# Arduino_Basic_Sensor_Board.net
KiCad netlist of a schematic drawn in EAGLE
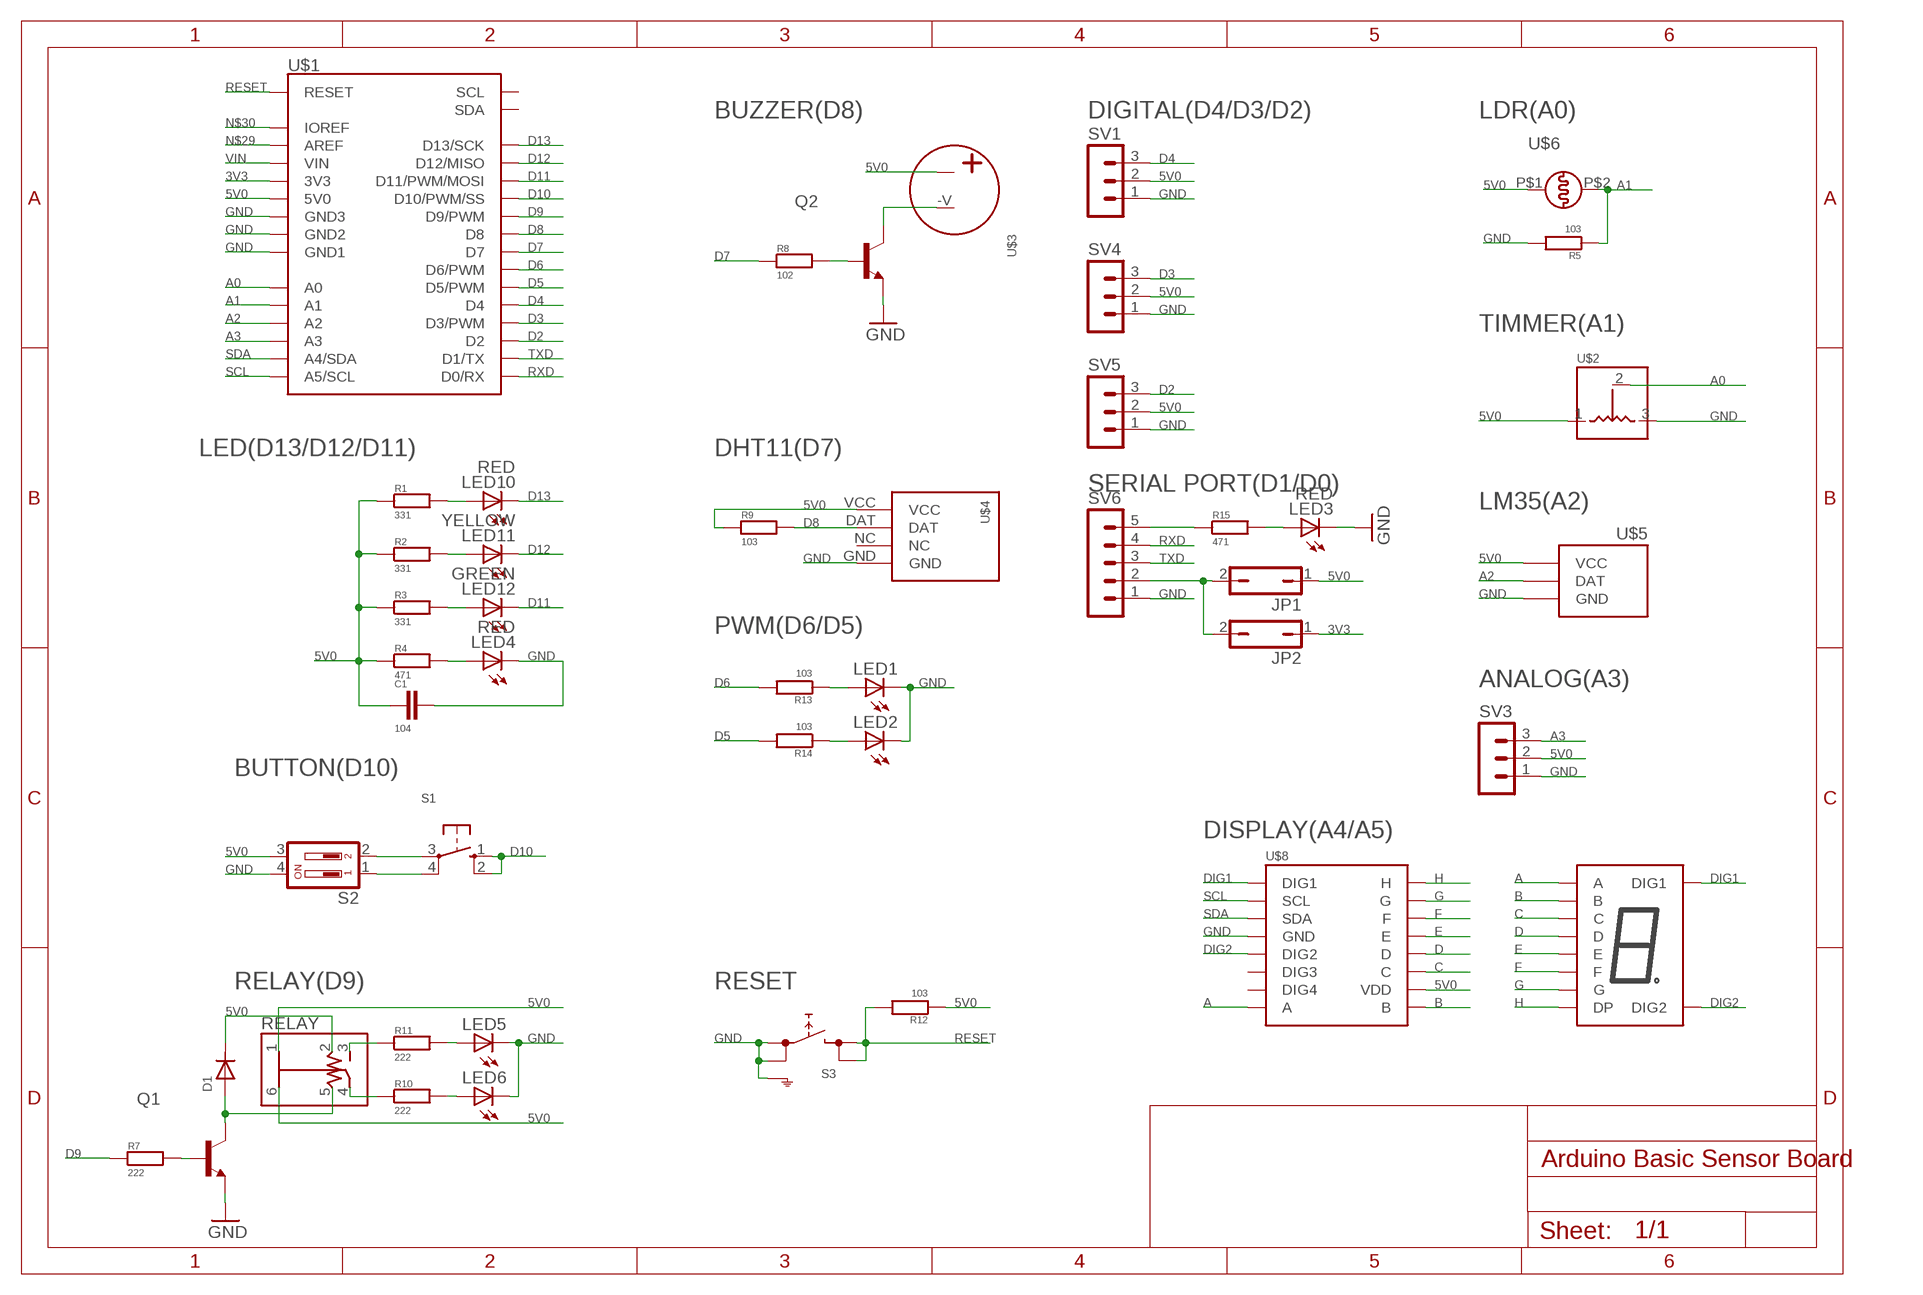
[diagram p0: schematic, sheet 1]

(export (version "E")
  (design (tool "Eeschema 10.0.6"))
  (components
    (comp (ref "C1")
      (value "104")
      (footprint "eagle-import:C0805")
      (libsource (lib "eagle-import") (part "C0805"))
    )
    (comp (ref "D1")
      (value "DIODESMB")
      (footprint "eagle-import:SMB")
      (libsource (lib "eagle-import") (part "DIODESMB"))
    )
    (comp (ref "JP1")
      (value "JP1Q")
      (footprint "eagle-import:JP1Q")
      (libsource (lib "eagle-import") (part "JP1Q"))
    )
    (comp (ref "JP2")
      (value "JP1Q")
      (footprint "eagle-import:JP1Q")
      (libsource (lib "eagle-import") (part "JP1Q"))
    )
    (comp (ref "LED1")
      (value "LEDCHIPLED_1206")
      (footprint "eagle-import:LED1206")
      (libsource (lib "eagle-import") (part "LEDCHIPLED_1206"))
    )
    (comp (ref "LED2")
      (value "LEDCHIPLED_1206")
      (footprint "eagle-import:LED1206")
      (libsource (lib "eagle-import") (part "LEDCHIPLED_1206"))
    )
    (comp (ref "LED3")
      (value "RED")
      (footprint "eagle-import:LED0805")
      (libsource (lib "eagle-import") (part "LEDCHIPLED_0805"))
    )
    (comp (ref "LED4")
      (value "RED")
      (footprint "eagle-import:LED0805")
      (libsource (lib "eagle-import") (part "LEDCHIPLED_0805"))
    )
    (comp (ref "LED5")
      (value "LEDSML1206")
      (footprint "eagle-import:SML1206")
      (libsource (lib "eagle-import") (part "LEDSML1206"))
    )
    (comp (ref "LED6")
      (value "LEDSML1206")
      (footprint "eagle-import:SML1206")
      (libsource (lib "eagle-import") (part "LEDSML1206"))
    )
    (comp (ref "LED10")
      (value "RED")
      (footprint "eagle-import:SML1206")
      (libsource (lib "eagle-import") (part "LEDSML1206"))
    )
    (comp (ref "LED11")
      (value "YELLOW")
      (footprint "eagle-import:SML1206")
      (libsource (lib "eagle-import") (part "LEDSML1206"))
    )
    (comp (ref "LED12")
      (value "GREEN")
      (footprint "eagle-import:SML1206")
      (libsource (lib "eagle-import") (part "LEDSML1206"))
    )
    (comp (ref "Q1")
      (value "S8050SOT23")
      (footprint "eagle-import:SOT23")
      (libsource (lib "eagle-import") (part "S8050SOT23"))
    )
    (comp (ref "Q2")
      (value "S8050SOT23")
      (footprint "eagle-import:SOT23")
      (libsource (lib "eagle-import") (part "S8050SOT23"))
    )
    (comp (ref "R1")
      (value "331")
      (footprint "eagle-import:R0805")
      (libsource (lib "eagle-import") (part "R0805"))
    )
    (comp (ref "R2")
      (value "331")
      (footprint "eagle-import:R0805")
      (libsource (lib "eagle-import") (part "R0805"))
    )
    (comp (ref "R3")
      (value "331")
      (footprint "eagle-import:R0805")
      (libsource (lib "eagle-import") (part "R0805"))
    )
    (comp (ref "R4")
      (value "471")
      (footprint "eagle-import:R0805")
      (libsource (lib "eagle-import") (part "R0805"))
    )
    (comp (ref "R5")
      (value "103")
      (footprint "eagle-import:R0805")
      (libsource (lib "eagle-import") (part "R0805"))
    )
    (comp (ref "R7")
      (value "222")
      (footprint "eagle-import:R0805")
      (libsource (lib "eagle-import") (part "R0805"))
    )
    (comp (ref "R8")
      (value "102")
      (footprint "eagle-import:R0805")
      (libsource (lib "eagle-import") (part "R0805"))
    )
    (comp (ref "R9")
      (value "103")
      (footprint "eagle-import:R0805")
      (libsource (lib "eagle-import") (part "R0805"))
    )
    (comp (ref "R10")
      (value "222")
      (footprint "eagle-import:R0805")
      (libsource (lib "eagle-import") (part "R0805"))
    )
    (comp (ref "R11")
      (value "222")
      (footprint "eagle-import:R0805")
      (libsource (lib "eagle-import") (part "R0805"))
    )
    (comp (ref "R12")
      (value "103")
      (footprint "eagle-import:R0805")
      (libsource (lib "eagle-import") (part "R0805"))
    )
    (comp (ref "R13")
      (value "103")
      (footprint "eagle-import:R0805")
      (libsource (lib "eagle-import") (part "R0805"))
    )
    (comp (ref "R14")
      (value "103")
      (footprint "eagle-import:R0805")
      (libsource (lib "eagle-import") (part "R0805"))
    )
    (comp (ref "R15")
      (value "471")
      (footprint "eagle-import:R0805")
      (libsource (lib "eagle-import") (part "R0805"))
    )
    (comp (ref "RELAY")
      (value "RELAY-HK4100F-DC5V")
      (footprint "eagle-import:RELAY-HK4100F-DC5V")
      (libsource (lib "eagle-import") (part "RELAY-HK4100F-DC5V"))
    )
    (comp (ref "S1")
      (value "TS-DIP-4.54.5")
      (footprint "eagle-import:TS-DIP-4.5_4.5")
      (fields (field (name "MPN") "B3F-1000"))
      (libsource (lib "eagle-import") (part "TS-DIP-4.54.5"))
    )
    (comp (ref "S2")
      (value "SD4-02")
      (footprint "eagle-import:SD4-02")
      (libsource (lib "eagle-import") (part "SD4-02"))
    )
    (comp (ref "S3")
      (value "TS-SMD_6S6_SHIELD")
      (footprint "eagle-import:TS-SMD_6_6_SHIELD")
      (libsource (lib "eagle-import") (part "TS-SMD_66_SHIELDS"))
    )
    (comp (ref "SV1")
      (value "MA03-1")
      (footprint "eagle-import:MA03-1")
      (libsource (lib "eagle-import") (part "MA03-1"))
    )
    (comp (ref "SV3")
      (value "MA03-1")
      (footprint "eagle-import:MA03-1")
      (libsource (lib "eagle-import") (part "MA03-1"))
    )
    (comp (ref "SV4")
      (value "MA03-1")
      (footprint "eagle-import:MA03-1")
      (libsource (lib "eagle-import") (part "MA03-1"))
    )
    (comp (ref "SV5")
      (value "MA03-1")
      (footprint "eagle-import:MA03-1")
      (libsource (lib "eagle-import") (part "MA03-1"))
    )
    (comp (ref "SV6")
      (value "MA05-1")
      (footprint "eagle-import:MA05-1")
      (libsource (lib "eagle-import") (part "MA05-1"))
    )
    (comp (ref "U$1")
      (value "ARDUINO-UNO")
      (footprint "eagle-import:ARDUINO-UNO")
      (libsource (lib "eagle-import") (part "ARDUINO-UNO"))
    )
    (comp (ref "U$2")
      (value "33623362")
      (footprint "eagle-import:3362")
      (libsource (lib "eagle-import") (part "33623362"))
    )
    (comp (ref "U$3")
      (value "BUZZER")
      (footprint "eagle-import:BUZZER")
      (libsource (lib "eagle-import") (part "BUZZER"))
    )
    (comp (ref "U$4")
      (value "DHT11")
      (footprint "eagle-import:DHT11")
      (libsource (lib "eagle-import") (part "DHT11"))
    )
    (comp (ref "U$5")
      (value "LM35")
      (footprint "eagle-import:TO92")
      (libsource (lib "eagle-import") (part "LM35"))
    )
    (comp (ref "U$6")
      (value "LDR")
      (footprint "eagle-import:LDR")
      (libsource (lib "eagle-import") (part "LDR"))
    )
    (comp (ref "U$8")
      (value "TM1650")
      (footprint "eagle-import:SOP16")
      (libsource (lib "eagle-import") (part "TM1650"))
    )
    (comp (ref "U$15")
      (value "3261AS")
      (footprint "eagle-import:TN_AS_2_0.36INCH")
      (libsource (lib "eagle-import") (part "3261AS"))
    )
  )
  (nets
    (net (code "1") (name "/3V3") (class "Default")
      (node (ref "JP2") (pin "1") (pinfunction "1_1") (pintype "passive"))
      (node (ref "U$1") (pin "3V3") (pinfunction "3V3_3V3") (pintype "bidirectional"))
    )
    (net (code "2") (name "/5V0") (class "Default")
      (node (ref "C1") (pin "2") (pinfunction "2_2") (pintype "bidirectional"))
      (node (ref "D1") (pin "1") (pinfunction "1_1") (pintype "bidirectional"))
      (node (ref "JP1") (pin "1") (pinfunction "1_1") (pintype "passive"))
      (node (ref "R1") (pin "1") (pinfunction "1_1") (pintype "bidirectional"))
      (node (ref "R12") (pin "1") (pinfunction "1_1") (pintype "bidirectional"))
      (node (ref "R2") (pin "1") (pinfunction "1_1") (pintype "bidirectional"))
      (node (ref "R3") (pin "1") (pinfunction "1_1") (pintype "bidirectional"))
      (node (ref "R4") (pin "1") (pinfunction "1_1") (pintype "bidirectional"))
      (node (ref "R9") (pin "1") (pinfunction "1_1") (pintype "bidirectional"))
      (node (ref "RELAY") (pin "1") (pinfunction "1_1") (pintype "bidirectional"))
      (node (ref "RELAY") (pin "2") (pinfunction "2_2") (pintype "bidirectional"))
      (node (ref "RELAY") (pin "6") (pinfunction "6_6") (pintype "bidirectional"))
      (node (ref "S2") (pin "3") (pinfunction "3_3") (pintype "passive"))
      (node (ref "SV1") (pin "2") (pinfunction "2_2") (pintype "passive"))
      (node (ref "SV3") (pin "2") (pinfunction "2_2") (pintype "passive"))
      (node (ref "SV4") (pin "2") (pinfunction "2_2") (pintype "passive"))
      (node (ref "SV5") (pin "2") (pinfunction "2_2") (pintype "passive"))
      (node (ref "U$1") (pin "5V0") (pinfunction "5V0_5V0") (pintype "bidirectional"))
      (node (ref "U$2") (pin "1") (pinfunction "1_1") (pintype "bidirectional"))
      (node (ref "U$3") (pin "+V") (pinfunction "+V_+V") (pintype "bidirectional"))
      (node (ref "U$4") (pin "VCC") (pinfunction "VCC_VCC") (pintype "bidirectional"))
      (node (ref "U$5") (pin "1") (pinfunction "VCC_1") (pintype "bidirectional"))
      (node (ref "U$6") (pin "P$1") (pinfunction "P$1_P$1") (pintype "bidirectional"))
      (node (ref "U$8") (pin "10") (pinfunction "VDD_10") (pintype "bidirectional"))
    )
    (net (code "3") (name "/A") (class "Default")
      (node (ref "U$15") (pin "3") (pinfunction "A_3") (pintype "bidirectional"))
      (node (ref "U$8") (pin "8") (pinfunction "A_8") (pintype "bidirectional"))
    )
    (net (code "4") (name "/A0") (class "Default")
      (node (ref "U$1") (pin "A0") (pinfunction "A0_A0") (pintype "bidirectional"))
      (node (ref "U$2") (pin "2") (pinfunction "2_2") (pintype "bidirectional"))
    )
    (net (code "5") (name "/A1") (class "Default")
      (node (ref "R5") (pin "1") (pinfunction "1_1") (pintype "bidirectional"))
      (node (ref "U$1") (pin "A1") (pinfunction "A1_A1") (pintype "bidirectional"))
      (node (ref "U$6") (pin "P$2") (pinfunction "P$2_P$2") (pintype "bidirectional"))
    )
    (net (code "6") (name "/A2") (class "Default")
      (node (ref "U$1") (pin "A2") (pinfunction "A2_A2") (pintype "bidirectional"))
      (node (ref "U$5") (pin "2") (pinfunction "DAT_2") (pintype "bidirectional"))
    )
    (net (code "7") (name "/A3") (class "Default")
      (node (ref "SV3") (pin "3") (pinfunction "3_3") (pintype "passive"))
      (node (ref "U$1") (pin "A3") (pinfunction "A3_A3") (pintype "bidirectional"))
    )
    (net (code "8") (name "/B") (class "Default")
      (node (ref "U$15") (pin "9") (pinfunction "B_9") (pintype "bidirectional"))
      (node (ref "U$8") (pin "9") (pinfunction "B_9") (pintype "bidirectional"))
    )
    (net (code "9") (name "/C") (class "Default")
      (node (ref "U$15") (pin "8") (pinfunction "C_8") (pintype "bidirectional"))
      (node (ref "U$8") (pin "11") (pinfunction "C_11") (pintype "bidirectional"))
    )
    (net (code "10") (name "/D") (class "Default")
      (node (ref "U$15") (pin "6") (pinfunction "D_6") (pintype "bidirectional"))
      (node (ref "U$8") (pin "12") (pinfunction "D_12") (pintype "bidirectional"))
    )
    (net (code "11") (name "/D2") (class "Default")
      (node (ref "SV5") (pin "3") (pinfunction "3_3") (pintype "passive"))
      (node (ref "U$1") (pin "D2") (pinfunction "D2_D2") (pintype "bidirectional"))
    )
    (net (code "12") (name "/D3") (class "Default")
      (node (ref "SV4") (pin "3") (pinfunction "3_3") (pintype "passive"))
      (node (ref "U$1") (pin "D3") (pinfunction "D3/PWM_D3") (pintype "bidirectional"))
    )
    (net (code "13") (name "/D4") (class "Default")
      (node (ref "SV1") (pin "3") (pinfunction "3_3") (pintype "passive"))
      (node (ref "U$1") (pin "D4") (pinfunction "D4_D4") (pintype "bidirectional"))
    )
    (net (code "14") (name "/D5") (class "Default")
      (node (ref "R14") (pin "2") (pinfunction "2_2") (pintype "bidirectional"))
      (node (ref "U$1") (pin "D5") (pinfunction "D5/PWM_D5") (pintype "bidirectional"))
    )
    (net (code "15") (name "/D6") (class "Default")
      (node (ref "R13") (pin "2") (pinfunction "2_2") (pintype "bidirectional"))
      (node (ref "U$1") (pin "D6") (pinfunction "D6/PWM_D6") (pintype "bidirectional"))
    )
    (net (code "16") (name "/D7") (class "Default")
      (node (ref "R8") (pin "1") (pinfunction "1_1") (pintype "bidirectional"))
      (node (ref "U$1") (pin "D7") (pinfunction "D7_D7") (pintype "bidirectional"))
    )
    (net (code "17") (name "/D8") (class "Default")
      (node (ref "R9") (pin "2") (pinfunction "2_2") (pintype "bidirectional"))
      (node (ref "U$1") (pin "D8") (pinfunction "D8_D8") (pintype "bidirectional"))
      (node (ref "U$4") (pin "DAT") (pinfunction "DAT_DAT") (pintype "bidirectional"))
    )
    (net (code "18") (name "/D9") (class "Default")
      (node (ref "R7") (pin "1") (pinfunction "1_1") (pintype "bidirectional"))
      (node (ref "U$1") (pin "D9") (pinfunction "D9/PWM_D9") (pintype "bidirectional"))
    )
    (net (code "19") (name "/D10") (class "Default")
      (node (ref "S1") (pin "1") (pinfunction "S_1") (pintype "passive"))
      (node (ref "S1") (pin "2") (pinfunction "S1_2") (pintype "passive"))
      (node (ref "U$1") (pin "D10") (pinfunction "D10/PWM/SS_D10") (pintype "bidirectional"))
    )
    (net (code "20") (name "/D11") (class "Default")
      (node (ref "LED12") (pin "C") (pinfunction "C_C") (pintype "passive"))
      (node (ref "U$1") (pin "D11") (pinfunction "D11/PWM/MOSI_D11") (pintype "bidirectional"))
    )
    (net (code "21") (name "/D12") (class "Default")
      (node (ref "LED11") (pin "C") (pinfunction "C_C") (pintype "passive"))
      (node (ref "U$1") (pin "D12") (pinfunction "D12/MISO_D12") (pintype "bidirectional"))
    )
    (net (code "22") (name "/D13") (class "Default")
      (node (ref "LED10") (pin "C") (pinfunction "C_C") (pintype "passive"))
      (node (ref "U$1") (pin "D13") (pinfunction "D13/SCK_D13") (pintype "bidirectional"))
    )
    (net (code "23") (name "/DIG1") (class "Default")
      (node (ref "U$15") (pin "10") (pinfunction "DIG1_10") (pintype "bidirectional"))
      (node (ref "U$8") (pin "1") (pinfunction "DIG1_1") (pintype "bidirectional"))
    )
    (net (code "24") (name "/DIG2") (class "Default")
      (node (ref "U$15") (pin "5") (pinfunction "DIG2_5") (pintype "bidirectional"))
      (node (ref "U$8") (pin "5") (pinfunction "DIG2_5") (pintype "bidirectional"))
    )
    (net (code "25") (name "/E") (class "Default")
      (node (ref "U$15") (pin "7") (pinfunction "E_7") (pintype "bidirectional"))
      (node (ref "U$8") (pin "13") (pinfunction "E_13") (pintype "bidirectional"))
    )
    (net (code "26") (name "/F") (class "Default")
      (node (ref "U$15") (pin "4") (pinfunction "F_4") (pintype "bidirectional"))
      (node (ref "U$8") (pin "14") (pinfunction "F_14") (pintype "bidirectional"))
    )
    (net (code "27") (name "/G") (class "Default")
      (node (ref "U$15") (pin "1") (pinfunction "G_1") (pintype "bidirectional"))
      (node (ref "U$8") (pin "15") (pinfunction "G_15") (pintype "bidirectional"))
    )
    (net (code "28") (name "/H") (class "Default")
      (node (ref "U$15") (pin "2") (pinfunction "DP_2") (pintype "bidirectional"))
      (node (ref "U$8") (pin "16") (pinfunction "H_16") (pintype "bidirectional"))
    )
    (net (code "29") (name "/N$29") (class "Default")
      (node (ref "U$1") (pin "AREF") (pinfunction "AREF_AREF") (pintype "bidirectional"))
    )
    (net (code "30") (name "/N$30") (class "Default")
      (node (ref "U$1") (pin "REF") (pinfunction "IOREF_REF") (pintype "bidirectional"))
    )
    (net (code "31") (name "/RESET") (class "Default")
      (node (ref "R12") (pin "2") (pinfunction "2_2") (pintype "bidirectional"))
      (node (ref "S3") (pin "3") (pinfunction "2.1_3") (pintype "passive"))
      (node (ref "S3") (pin "4") (pinfunction "2.2_4") (pintype "passive"))
      (node (ref "U$1") (pin "RST") (pinfunction "RESET_RST") (pintype "bidirectional"))
    )
    (net (code "32") (name "/RXD") (class "Default")
      (node (ref "SV6") (pin "4") (pinfunction "4_4") (pintype "passive"))
      (node (ref "U$1") (pin "D0") (pinfunction "D0/RX_D0") (pintype "bidirectional"))
    )
    (net (code "33") (name "/SCL") (class "Default")
      (node (ref "U$1") (pin "A5") (pinfunction "A5/SCL_A5") (pintype "bidirectional"))
      (node (ref "U$8") (pin "2") (pinfunction "SCL_2") (pintype "bidirectional"))
    )
    (net (code "34") (name "/SDA") (class "Default")
      (node (ref "U$1") (pin "A4") (pinfunction "A4/SDA_A4") (pintype "bidirectional"))
      (node (ref "U$8") (pin "3") (pinfunction "SDA_3") (pintype "bidirectional"))
    )
    (net (code "35") (name "/TXD") (class "Default")
      (node (ref "SV6") (pin "3") (pinfunction "3_3") (pintype "passive"))
      (node (ref "U$1") (pin "D1") (pinfunction "D1/TX_D1") (pintype "bidirectional"))
    )
    (net (code "36") (name "/VIN") (class "Default")
      (node (ref "U$1") (pin "VIN") (pinfunction "VIN_VIN") (pintype "bidirectional"))
    )
    (net (code "37") (name "GND") (class "Default")
      (node (ref "C1") (pin "1") (pinfunction "1_1") (pintype "bidirectional"))
      (node (ref "LED1") (pin "C") (pinfunction "C_C") (pintype "passive"))
      (node (ref "LED2") (pin "C") (pinfunction "C_C") (pintype "passive"))
      (node (ref "LED3") (pin "C") (pinfunction "C_C") (pintype "passive"))
      (node (ref "LED4") (pin "C") (pinfunction "C_C") (pintype "passive"))
      (node (ref "LED5") (pin "C") (pinfunction "C_C") (pintype "passive"))
      (node (ref "LED6") (pin "C") (pinfunction "C_C") (pintype "passive"))
      (node (ref "Q1") (pin "E") (pinfunction "E_E") (pintype "passive"))
      (node (ref "Q2") (pin "E") (pinfunction "E_E") (pintype "passive"))
      (node (ref "R5") (pin "2") (pinfunction "2_2") (pintype "bidirectional"))
      (node (ref "S2") (pin "4") (pinfunction "4_4") (pintype "passive"))
      (node (ref "S3") (pin "1") (pinfunction "1.1_1") (pintype "passive"))
      (node (ref "S3") (pin "2") (pinfunction "1.2_2") (pintype "passive"))
      (node (ref "S3") (pin "5") (pinfunction "SH_5") (pintype "passive"))
      (node (ref "SV1") (pin "1") (pinfunction "1_1") (pintype "passive"))
      (node (ref "SV3") (pin "1") (pinfunction "1_1") (pintype "passive"))
      (node (ref "SV4") (pin "1") (pinfunction "1_1") (pintype "passive"))
      (node (ref "SV5") (pin "1") (pinfunction "1_1") (pintype "passive"))
      (node (ref "SV6") (pin "1") (pinfunction "1_1") (pintype "passive"))
      (node (ref "U$1") (pin "GND1") (pinfunction "GND1_GND1") (pintype "bidirectional"))
      (node (ref "U$1") (pin "GND2") (pinfunction "GND2_GND2") (pintype "bidirectional"))
      (node (ref "U$1") (pin "GND3") (pinfunction "GND3_GND3") (pintype "bidirectional"))
      (node (ref "U$2") (pin "3") (pinfunction "3_3") (pintype "bidirectional"))
      (node (ref "U$4") (pin "GND") (pinfunction "GND_GND") (pintype "bidirectional"))
      (node (ref "U$5") (pin "3") (pinfunction "GND_3") (pintype "bidirectional"))
      (node (ref "U$8") (pin "4") (pinfunction "GND_4") (pintype "bidirectional"))
    )
    (net (code "38") (name "Net-(D1-Pad2)") (class "Default")
      (node (ref "D1") (pin "2") (pinfunction "2_2") (pintype "bidirectional"))
      (node (ref "Q1") (pin "C") (pinfunction "C_C") (pintype "passive"))
      (node (ref "RELAY") (pin "5") (pinfunction "5_5") (pintype "bidirectional"))
    )
    (net (code "39") (name "Net-(JP1-Pad2)") (class "Default")
      (node (ref "JP1") (pin "2") (pinfunction "2_2") (pintype "passive"))
      (node (ref "JP2") (pin "2") (pinfunction "2_2") (pintype "passive"))
      (node (ref "SV6") (pin "2") (pinfunction "2_2") (pintype "passive"))
    )
    (net (code "40") (name "Net-(LED1-PadA)") (class "Default")
      (node (ref "LED1") (pin "A") (pinfunction "A_A") (pintype "passive"))
      (node (ref "R13") (pin "1") (pinfunction "1_1") (pintype "bidirectional"))
    )
    (net (code "41") (name "Net-(LED2-PadA)") (class "Default")
      (node (ref "LED2") (pin "A") (pinfunction "A_A") (pintype "passive"))
      (node (ref "R14") (pin "1") (pinfunction "1_1") (pintype "bidirectional"))
    )
    (net (code "42") (name "Net-(LED3-PadA)") (class "Default")
      (node (ref "LED3") (pin "A") (pinfunction "A_A") (pintype "passive"))
      (node (ref "R15") (pin "2") (pinfunction "2_2") (pintype "bidirectional"))
    )
    (net (code "43") (name "Net-(LED4-PadA)") (class "Default")
      (node (ref "LED4") (pin "A") (pinfunction "A_A") (pintype "passive"))
      (node (ref "R4") (pin "2") (pinfunction "2_2") (pintype "bidirectional"))
    )
    (net (code "44") (name "Net-(LED5-PadA)") (class "Default")
      (node (ref "LED5") (pin "A") (pinfunction "A_A") (pintype "passive"))
      (node (ref "R11") (pin "2") (pinfunction "2_2") (pintype "bidirectional"))
    )
    (net (code "45") (name "Net-(LED6-PadA)") (class "Default")
      (node (ref "LED6") (pin "A") (pinfunction "A_A") (pintype "passive"))
      (node (ref "R10") (pin "2") (pinfunction "2_2") (pintype "bidirectional"))
    )
    (net (code "46") (name "Net-(LED10-PadA)") (class "Default")
      (node (ref "LED10") (pin "A") (pinfunction "A_A") (pintype "passive"))
      (node (ref "R1") (pin "2") (pinfunction "2_2") (pintype "bidirectional"))
    )
    (net (code "47") (name "Net-(LED11-PadA)") (class "Default")
      (node (ref "LED11") (pin "A") (pinfunction "A_A") (pintype "passive"))
      (node (ref "R2") (pin "2") (pinfunction "2_2") (pintype "bidirectional"))
    )
    (net (code "48") (name "Net-(LED12-PadA)") (class "Default")
      (node (ref "LED12") (pin "A") (pinfunction "A_A") (pintype "passive"))
      (node (ref "R3") (pin "2") (pinfunction "2_2") (pintype "bidirectional"))
    )
    (net (code "49") (name "Net-(Q1-PadB)") (class "Default")
      (node (ref "Q1") (pin "B") (pinfunction "B_B") (pintype "passive"))
      (node (ref "R7") (pin "2") (pinfunction "2_2") (pintype "bidirectional"))
    )
    (net (code "50") (name "Net-(Q2-PadB)") (class "Default")
      (node (ref "Q2") (pin "B") (pinfunction "B_B") (pintype "passive"))
      (node (ref "R8") (pin "2") (pinfunction "2_2") (pintype "bidirectional"))
    )
    (net (code "51") (name "Net-(Q2-PadC)") (class "Default")
      (node (ref "Q2") (pin "C") (pinfunction "C_C") (pintype "passive"))
      (node (ref "U$3") (pin "-V") (pinfunction "-V_-V") (pintype "bidirectional"))
    )
    (net (code "52") (name "Net-(R10-Pad1)") (class "Default")
      (node (ref "R10") (pin "1") (pinfunction "1_1") (pintype "bidirectional"))
      (node (ref "RELAY") (pin "4") (pinfunction "4_4") (pintype "bidirectional"))
    )
    (net (code "53") (name "Net-(R11-Pad1)") (class "Default")
      (node (ref "R11") (pin "1") (pinfunction "1_1") (pintype "bidirectional"))
      (node (ref "RELAY") (pin "3") (pinfunction "3_3") (pintype "bidirectional"))
    )
    (net (code "54") (name "Net-(R15-Pad1)") (class "Default")
      (node (ref "R15") (pin "1") (pinfunction "1_1") (pintype "bidirectional"))
      (node (ref "SV6") (pin "5") (pinfunction "5_5") (pintype "passive"))
    )
    (net (code "55") (name "Net-(S1-P)") (class "Default")
      (node (ref "S1") (pin "3") (pinfunction "P_3") (pintype "passive"))
      (node (ref "S2") (pin "2") (pinfunction "2_2") (pintype "passive"))
    )
    (net (code "56") (name "Net-(S1-P1)") (class "Default")
      (node (ref "S1") (pin "4") (pinfunction "P1_4") (pintype "passive"))
      (node (ref "S2") (pin "1") (pinfunction "1_1") (pintype "passive"))
    )
    (net (code "57") (name "unconnected-(U$1-PadSCL)") (class "Default")
      (node (ref "U$1") (pin "SCL") (pinfunction "SCL_SCL") (pintype "bidirectional"))
    )
    (net (code "58") (name "unconnected-(U$1-PadSDA)") (class "Default")
      (node (ref "U$1") (pin "SDA") (pinfunction "SDA_SDA") (pintype "bidirectional"))
    )
    (net (code "59") (name "unconnected-(U$4-PadNC)") (class "Default")
      (node (ref "U$4") (pin "NC") (pinfunction "NC_NC") (pintype "bidirectional"))
    )
    (net (code "60") (name "unconnected-(U$8-DIG3-Pad6)") (class "Default")
      (node (ref "U$8") (pin "6") (pinfunction "DIG3_6") (pintype "bidirectional"))
    )
    (net (code "61") (name "unconnected-(U$8-DIG4-Pad7)") (class "Default")
      (node (ref "U$8") (pin "7") (pinfunction "DIG4_7") (pintype "bidirectional"))
    )
  )
)
